# USB2_0.net
KiCad netlist of a schematic drawn in Altium Designer
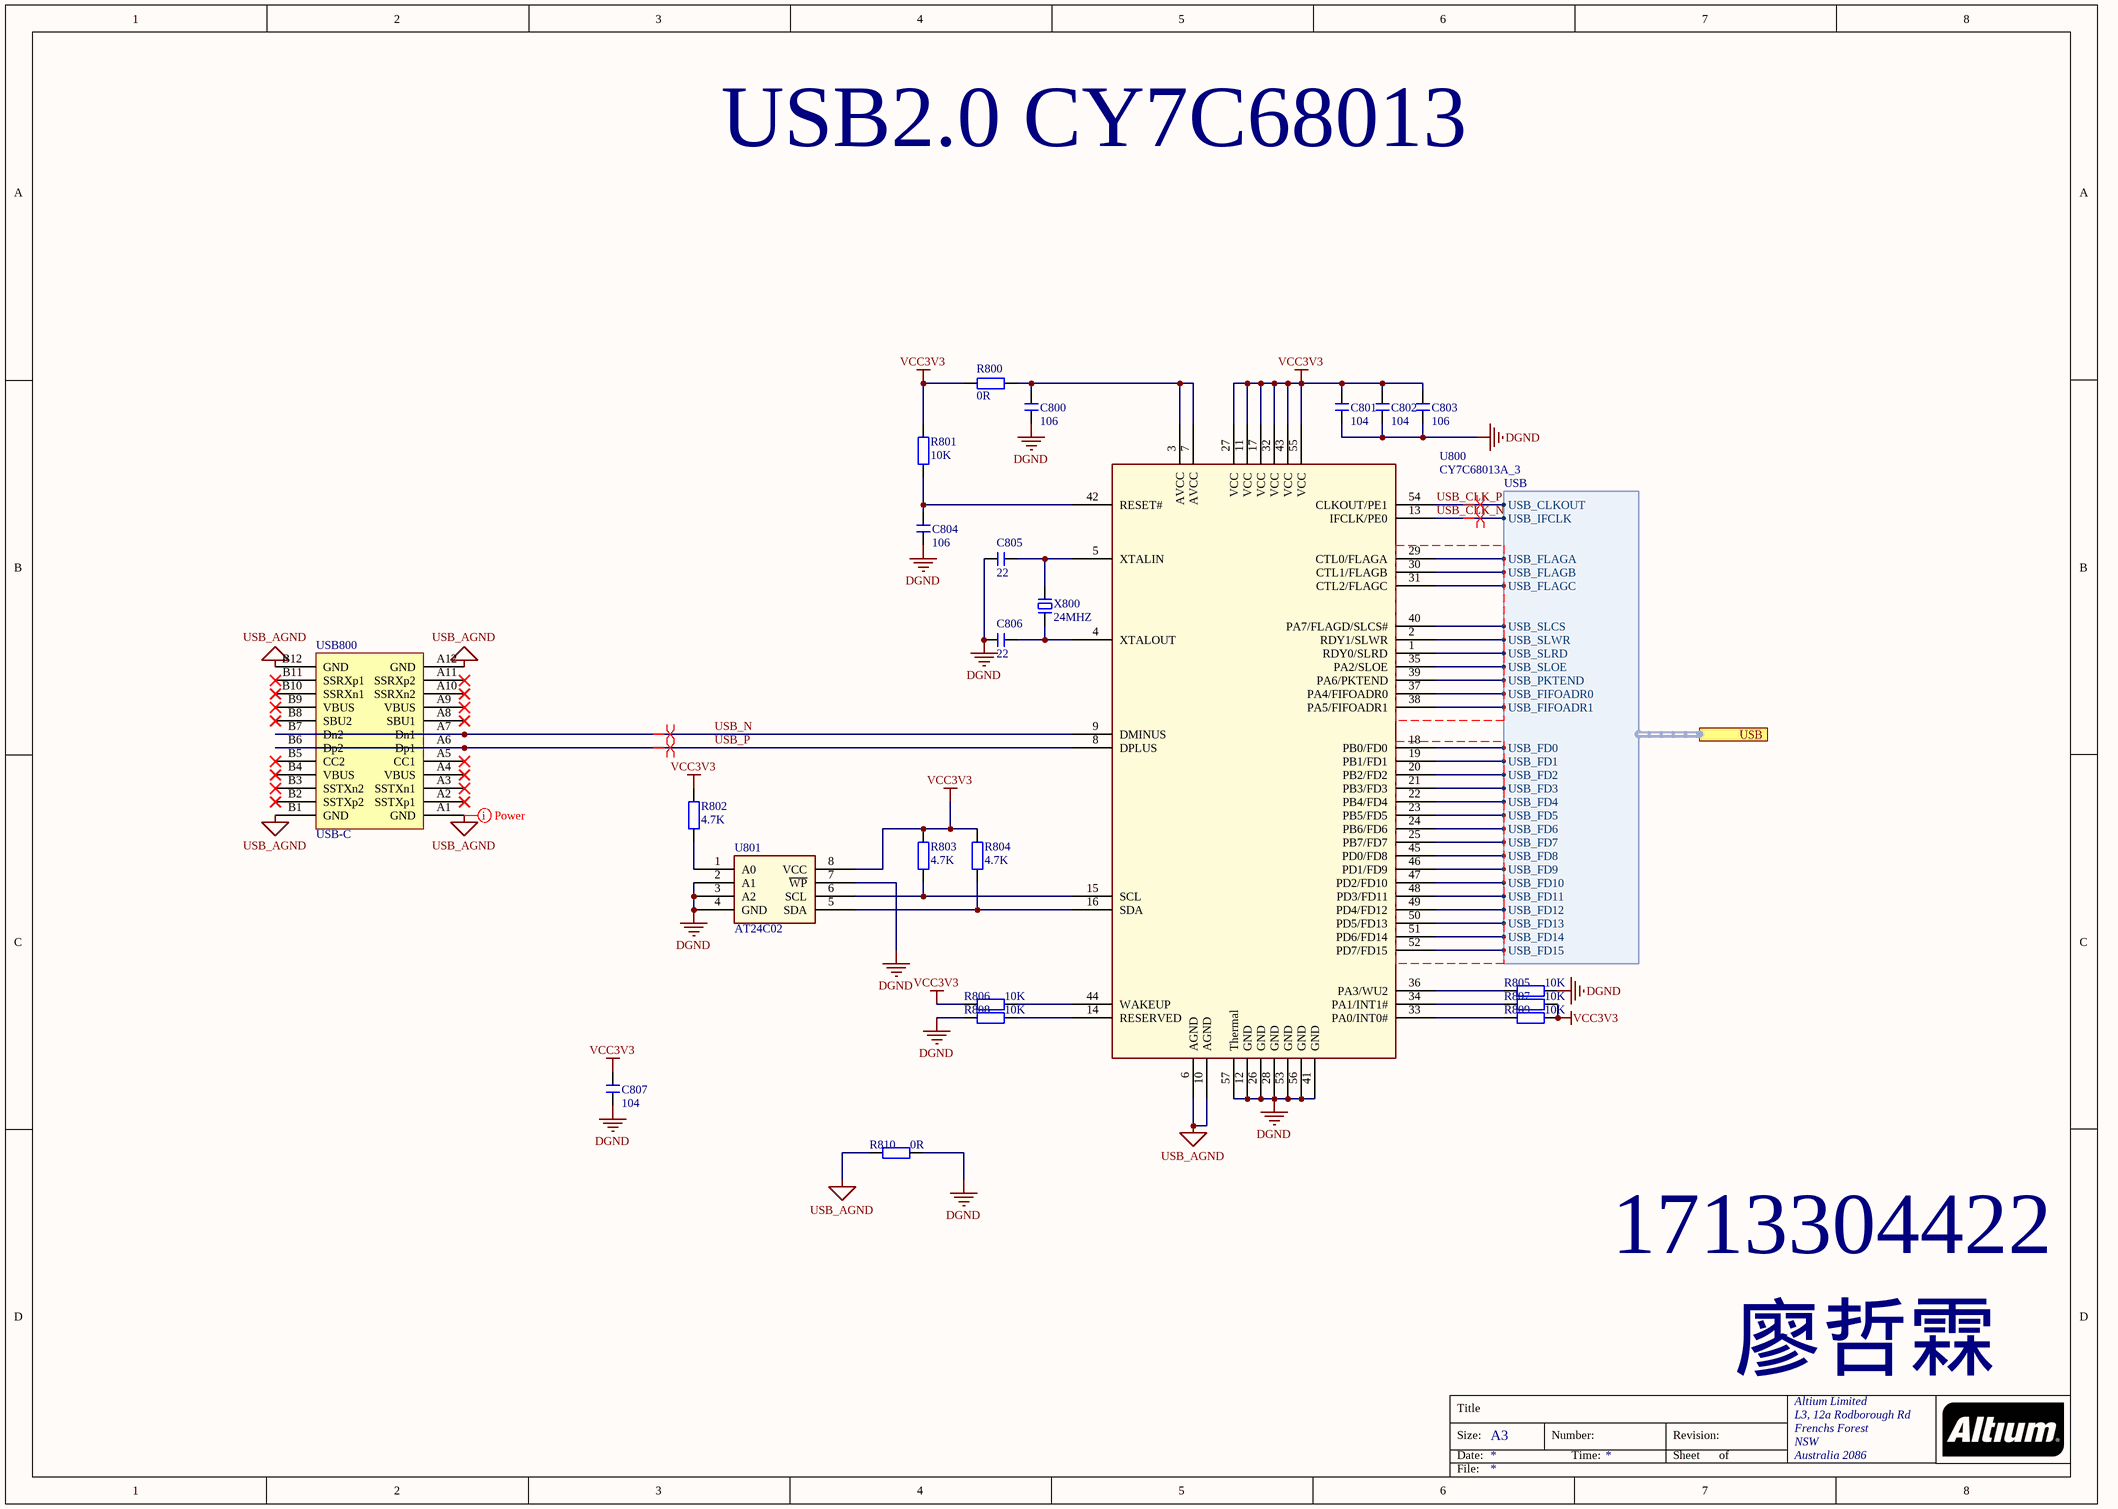
[diagram p0: USB2.0.SchDoc]

(export (version "E")
  (design (tool "Eeschema 10.0.6"))
  (components
    (comp (ref "C800")
      (value "106")
      (footprint "C 0402_M")
      (description "无极性贴片电容")
      (fields (field (name "版权归属") "源创客"))
      (libsource (lib "3.1   - 电阻-电容-电感") (part "C"))
    )
    (comp (ref "C801")
      (value "104")
      (footprint "C 0402_M")
      (description "无极性贴片电容")
      (fields (field (name "版权归属") "源创客"))
      (libsource (lib "3.1   - 电阻-电容-电感") (part "C"))
    )
    (comp (ref "C802")
      (value "104")
      (footprint "C 0402_M")
      (description "无极性贴片电容")
      (fields (field (name "版权归属") "源创客"))
      (libsource (lib "3.1   - 电阻-电容-电感") (part "C"))
    )
    (comp (ref "C803")
      (value "106")
      (footprint "C 0402_M")
      (description "无极性贴片电容")
      (fields (field (name "版权归属") "源创客"))
      (libsource (lib "3.1   - 电阻-电容-电感") (part "C"))
    )
    (comp (ref "C804")
      (value "106")
      (footprint "C 0402_M")
      (description "无极性贴片电容")
      (fields (field (name "版权归属") "源创客"))
      (libsource (lib "3.1   - 电阻-电容-电感") (part "C"))
    )
    (comp (ref "C805")
      (value "22")
      (footprint "C 0402_M")
      (description "无极性贴片电容")
      (fields (field (name "版权归属") "源创客"))
      (libsource (lib "3.1   - 电阻-电容-电感") (part "C"))
    )
    (comp (ref "C806")
      (value "22")
      (footprint "C 0402_M")
      (description "无极性贴片电容")
      (fields (field (name "版权归属") "源创客"))
      (libsource (lib "3.1   - 电阻-电容-电感") (part "C"))
    )
    (comp (ref "C807")
      (value "104")
      (footprint "C 0402_M")
      (description "无极性贴片电容")
      (fields (field (name "版权归属") "源创客"))
      (libsource (lib "3.1   - 电阻-电容-电感") (part "C"))
    )
    (comp (ref "R800")
      (value "0R")
      (footprint "R 0402_M")
      (description "贴片电阻")
      (fields (field (name "版权归属") "源创客"))
      (libsource (lib "3.1   - 电阻-电容-电感") (part "R"))
    )
    (comp (ref "R801")
      (value "10K")
      (footprint "R 0402_M")
      (description "贴片电阻")
      (fields (field (name "版权归属") "源创客"))
      (libsource (lib "3.1   - 电阻-电容-电感") (part "R"))
    )
    (comp (ref "R802")
      (value "4.7K")
      (footprint "R 0402_M")
      (description "贴片电阻")
      (fields (field (name "版权归属") "源创客"))
      (libsource (lib "3.1   - 电阻-电容-电感") (part "R"))
    )
    (comp (ref "R803")
      (value "4.7K")
      (footprint "R 0402_M")
      (description "贴片电阻")
      (fields (field (name "版权归属") "源创客"))
      (libsource (lib "3.1   - 电阻-电容-电感") (part "R"))
    )
    (comp (ref "R804")
      (value "4.7K")
      (footprint "R 0402_M")
      (description "贴片电阻")
      (fields (field (name "版权归属") "源创客"))
      (libsource (lib "3.1   - 电阻-电容-电感") (part "R"))
    )
    (comp (ref "R805")
      (value "10K")
      (footprint "R 0402_M")
      (description "贴片电阻")
      (fields (field (name "版权归属") "源创客"))
      (libsource (lib "3.1   - 电阻-电容-电感") (part "R"))
    )
    (comp (ref "R806")
      (value "10K")
      (footprint "R 0402_M")
      (description "贴片电阻")
      (fields (field (name "版权归属") "源创客"))
      (libsource (lib "3.1   - 电阻-电容-电感") (part "R"))
    )
    (comp (ref "R807")
      (value "10K")
      (footprint "R 0402_M")
      (description "贴片电阻")
      (fields (field (name "版权归属") "源创客"))
      (libsource (lib "3.1   - 电阻-电容-电感") (part "R"))
    )
    (comp (ref "R808")
      (value "10K")
      (footprint "R 0402_M")
      (description "贴片电阻")
      (fields (field (name "版权归属") "源创客"))
      (libsource (lib "3.1   - 电阻-电容-电感") (part "R"))
    )
    (comp (ref "R809")
      (value "10K")
      (footprint "R 0402_M")
      (description "贴片电阻")
      (fields (field (name "版权归属") "源创客"))
      (libsource (lib "3.1   - 电阻-电容-电感") (part "R"))
    )
    (comp (ref "R810")
      (value "0R")
      (footprint "R 0402_M")
      (description "贴片电阻")
      (fields (field (name "版权归属") "源创客"))
      (libsource (lib "3.1   - 电阻-电容-电感") (part "R"))
    )
    (comp (ref "U800")
      (value "CY7C68013A_3")
      (footprint "QFN50P800X800X100-57N")
      (libsource (lib "altium-import") (part "root_0_CY7C68013A_3_"))
    )
    (comp (ref "U801")
      (value "AT24C02")
      (footprint "SOP8_M")
      (libsource (lib "6_Layer_Library") (part "AT24C02"))
    )
    (comp (ref "USB800")
      (value "USB-C")
      (footprint "USB-C/S_A")
      (description "USB-C型母接口")
      (fields (field (name "版权归属") "源创客"))
      (libsource (lib "4.1   - 接口类") (part "USB-C/S"))
    )
    (comp (ref "X800")
      (value "24MHZ")
      (footprint "OSC 5032-2P")
      (description "2脚无源脚晶振")
      (fields (field (name "版权归属") "源创客"))
      (libsource (lib "10.1 - 保险丝-晶振") (part "XTAL-2P"))
    )
  )
  (nets
    (net (code "2") (name "/USB_CLK_N") (class "Default")
      (node (ref "U800") (pin "13") (pinfunction "IFCLK/PE0_13") (pintype "passive"))
    )
    (net (code "3") (name "/USB_CLK_P") (class "Default")
      (node (ref "U800") (pin "54") (pinfunction "CLKOUT/PE1_54") (pintype "passive"))
    )
    (net (code "4") (name "/USB_FD0") (class "Default")
      (node (ref "U800") (pin "18") (pinfunction "PB0/FD0_18") (pintype "passive"))
    )
    (net (code "5") (name "/USB_FD1") (class "Default")
      (node (ref "U800") (pin "19") (pinfunction "PB1/FD1_19") (pintype "passive"))
    )
    (net (code "6") (name "/USB_FD2") (class "Default")
      (node (ref "U800") (pin "20") (pinfunction "PB2/FD2_20") (pintype "passive"))
    )
    (net (code "7") (name "/USB_FD3") (class "Default")
      (node (ref "U800") (pin "21") (pinfunction "PB3/FD3_21") (pintype "passive"))
    )
    (net (code "8") (name "/USB_FD4") (class "Default")
      (node (ref "U800") (pin "22") (pinfunction "PB4/FD4_22") (pintype "passive"))
    )
    (net (code "9") (name "/USB_FD5") (class "Default")
      (node (ref "U800") (pin "23") (pinfunction "PB5/FD5_23") (pintype "passive"))
    )
    (net (code "10") (name "/USB_FD6") (class "Default")
      (node (ref "U800") (pin "24") (pinfunction "PB6/FD6_24") (pintype "passive"))
    )
    (net (code "11") (name "/USB_FD7") (class "Default")
      (node (ref "U800") (pin "25") (pinfunction "PB7/FD7_25") (pintype "passive"))
    )
    (net (code "12") (name "/USB_FD8") (class "Default")
      (node (ref "U800") (pin "45") (pinfunction "PD0/FD8_45") (pintype "passive"))
    )
    (net (code "13") (name "/USB_FD9") (class "Default")
      (node (ref "U800") (pin "46") (pinfunction "PD1/FD9_46") (pintype "passive"))
    )
    (net (code "14") (name "/USB_FD10") (class "Default")
      (node (ref "U800") (pin "47") (pinfunction "PD2/FD10_47") (pintype "passive"))
    )
    (net (code "15") (name "/USB_FD11") (class "Default")
      (node (ref "U800") (pin "48") (pinfunction "PD3/FD11_48") (pintype "passive"))
    )
    (net (code "16") (name "/USB_FD12") (class "Default")
      (node (ref "U800") (pin "49") (pinfunction "PD4/FD12_49") (pintype "passive"))
    )
    (net (code "17") (name "/USB_FD13") (class "Default")
      (node (ref "U800") (pin "50") (pinfunction "PD5/FD13_50") (pintype "passive"))
    )
    (net (code "18") (name "/USB_FD14") (class "Default")
      (node (ref "U800") (pin "51") (pinfunction "PD6/FD14_51") (pintype "passive"))
    )
    (net (code "19") (name "/USB_FD15") (class "Default")
      (node (ref "U800") (pin "52") (pinfunction "PD7/FD15_52") (pintype "passive"))
    )
    (net (code "20") (name "/USB_FIFOADR0") (class "Default")
      (node (ref "U800") (pin "37") (pinfunction "PA4/FIFOADR0_37") (pintype "passive"))
    )
    (net (code "21") (name "/USB_FIFOADR1") (class "Default")
      (node (ref "U800") (pin "38") (pinfunction "PA5/FIFOADR1_38") (pintype "passive"))
    )
    (net (code "22") (name "/USB_FLAGA") (class "Default")
      (node (ref "U800") (pin "29") (pinfunction "CTL0/FLAGA_29") (pintype "passive"))
    )
    (net (code "23") (name "/USB_FLAGB") (class "Default")
      (node (ref "U800") (pin "30") (pinfunction "CTL1/FLAGB_30") (pintype "passive"))
    )
    (net (code "24") (name "/USB_FLAGC") (class "Default")
      (node (ref "U800") (pin "31") (pinfunction "CTL2/FLAGC_31") (pintype "passive"))
    )
    (net (code "25") (name "/USB_N") (class "Default")
      (node (ref "U800") (pin "9") (pinfunction "DMINUS_9") (pintype "passive"))
      (node (ref "USB800") (pin "A7") (pinfunction "Dn1_A7") (pintype "passive"))
      (node (ref "USB800") (pin "B7") (pinfunction "Dn2_B7") (pintype "passive"))
    )
    (net (code "26") (name "/USB_P") (class "Default")
      (node (ref "U800") (pin "8") (pinfunction "DPLUS_8") (pintype "passive"))
      (node (ref "USB800") (pin "A6") (pinfunction "Dp1_A6") (pintype "passive"))
      (node (ref "USB800") (pin "B6") (pinfunction "Dp2_B6") (pintype "passive"))
    )
    (net (code "27") (name "/USB_PKTEND") (class "Default")
      (node (ref "U800") (pin "39") (pinfunction "PA6/PKTEND_39") (pintype "passive"))
    )
    (net (code "28") (name "/USB_SLCS") (class "Default")
      (node (ref "U800") (pin "40") (pinfunction "PA7/FLAGD/SLCS#_40") (pintype "passive"))
    )
    (net (code "29") (name "/USB_SLOE") (class "Default")
      (node (ref "U800") (pin "35") (pinfunction "PA2/SLOE_35") (pintype "passive"))
    )
    (net (code "30") (name "/USB_SLRD") (class "Default")
      (node (ref "U800") (pin "1") (pinfunction "RDY0/SLRD_1") (pintype "passive"))
    )
    (net (code "31") (name "/USB_SLWR") (class "Default")
      (node (ref "U800") (pin "2") (pinfunction "RDY1/SLWR_2") (pintype "passive"))
    )
    (net (code "33") (name "DGND") (class "Default")
      (node (ref "C800") (pin "1") (pinfunction "1_1") (pintype "passive"))
      (node (ref "C801") (pin "1") (pinfunction "1_1") (pintype "passive"))
      (node (ref "C802") (pin "1") (pinfunction "1_1") (pintype "passive"))
      (node (ref "C803") (pin "1") (pinfunction "1_1") (pintype "passive"))
      (node (ref "C804") (pin "1") (pinfunction "1_1") (pintype "passive"))
      (node (ref "C805") (pin "2") (pinfunction "2_2") (pintype "passive"))
      (node (ref "C806") (pin "2") (pinfunction "2_2") (pintype "passive"))
      (node (ref "C807") (pin "2") (pinfunction "2_2") (pintype "passive"))
      (node (ref "R805") (pin "2") (pinfunction "2_2") (pintype "passive"))
      (node (ref "R808") (pin "1") (pinfunction "1_1") (pintype "passive"))
      (node (ref "R810") (pin "2") (pinfunction "2_2") (pintype "passive"))
      (node (ref "U800") (pin "12") (pinfunction "GND_12") (pintype "power_in"))
      (node (ref "U800") (pin "26") (pinfunction "GND_26") (pintype "power_in"))
      (node (ref "U800") (pin "28") (pinfunction "GND_28") (pintype "power_in"))
      (node (ref "U800") (pin "41") (pinfunction "GND_41") (pintype "power_in"))
      (node (ref "U800") (pin "53") (pinfunction "GND_53") (pintype "power_in"))
      (node (ref "U800") (pin "56") (pinfunction "GND_56") (pintype "power_in"))
      (node (ref "U800") (pin "57") (pinfunction "Thermal_57") (pintype "power_in"))
      (node (ref "U801") (pin "2") (pinfunction "A1_2") (pintype "power_in"))
      (node (ref "U801") (pin "3") (pinfunction "A2_3") (pintype "power_in"))
      (node (ref "U801") (pin "4") (pinfunction "GND_4") (pintype "passive"))
      (node (ref "U801") (pin "7") (pinfunction "~{WP}_7") (pintype "passive"))
    )
    (net (code "34") (name "Net-(C800-Pad2)") (class "Default")
      (node (ref "C800") (pin "2") (pinfunction "2_2") (pintype "passive"))
      (node (ref "R800") (pin "1") (pinfunction "1_1") (pintype "passive"))
      (node (ref "U800") (pin "3") (pinfunction "AVCC_3") (pintype "power_in"))
      (node (ref "U800") (pin "7") (pinfunction "AVCC_7") (pintype "power_in"))
    )
    (net (code "35") (name "Net-(U800-PA0{slash}INT0#)") (class "Default")
      (node (ref "R809") (pin "1") (pinfunction "1_1") (pintype "passive"))
      (node (ref "U800") (pin "33") (pinfunction "PA0/INT0#_33") (pintype "passive"))
    )
    (net (code "36") (name "Net-(U800-PA1{slash}INT1#)") (class "Default")
      (node (ref "R807") (pin "1") (pinfunction "1_1") (pintype "passive"))
      (node (ref "U800") (pin "34") (pinfunction "PA1/INT1#_34") (pintype "passive"))
    )
    (net (code "37") (name "Net-(U800-PA3{slash}WU2)") (class "Default")
      (node (ref "R805") (pin "1") (pinfunction "1_1") (pintype "passive"))
      (node (ref "U800") (pin "36") (pinfunction "PA3/WU2_36") (pintype "passive"))
    )
    (net (code "38") (name "Net-(U800-RESERVED)") (class "Default")
      (node (ref "R808") (pin "2") (pinfunction "2_2") (pintype "passive"))
      (node (ref "U800") (pin "14") (pinfunction "RESERVED_14") (pintype "passive"))
    )
    (net (code "39") (name "Net-(U800-RESET#)") (class "Default")
      (node (ref "C804") (pin "2") (pinfunction "2_2") (pintype "passive"))
      (node (ref "R801") (pin "2") (pinfunction "2_2") (pintype "passive"))
      (node (ref "U800") (pin "42") (pinfunction "RESET#_42") (pintype "power_in"))
    )
    (net (code "40") (name "Net-(U800-SCL)") (class "Default")
      (node (ref "R803") (pin "2") (pinfunction "2_2") (pintype "passive"))
      (node (ref "U800") (pin "15") (pinfunction "SCL_15") (pintype "passive"))
      (node (ref "U801") (pin "6") (pinfunction "SCL_6") (pintype "passive"))
    )
    (net (code "41") (name "Net-(U800-SDA)") (class "Default")
      (node (ref "R804") (pin "2") (pinfunction "2_2") (pintype "passive"))
      (node (ref "U800") (pin "16") (pinfunction "SDA_16") (pintype "passive"))
      (node (ref "U801") (pin "5") (pinfunction "SDA_5") (pintype "passive"))
    )
    (net (code "42") (name "Net-(U800-WAKEUP)") (class "Default")
      (node (ref "R806") (pin "2") (pinfunction "2_2") (pintype "passive"))
      (node (ref "U800") (pin "44") (pinfunction "WAKEUP_44") (pintype "passive"))
    )
    (net (code "43") (name "Net-(U800-XTALIN)") (class "Default")
      (node (ref "C805") (pin "1") (pinfunction "1_1") (pintype "passive"))
      (node (ref "U800") (pin "5") (pinfunction "XTALIN_5") (pintype "passive"))
      (node (ref "X800") (pin "2") (pinfunction "2_2") (pintype "passive"))
    )
    (net (code "44") (name "Net-(U800-XTALOUT)") (class "Default")
      (node (ref "C806") (pin "1") (pinfunction "1_1") (pintype "passive"))
      (node (ref "U800") (pin "4") (pinfunction "XTALOUT_4") (pintype "passive"))
      (node (ref "X800") (pin "1") (pinfunction "1_1") (pintype "passive"))
    )
    (net (code "45") (name "Net-(U801-A0)") (class "Default")
      (node (ref "R802") (pin "2") (pinfunction "2_2") (pintype "passive"))
      (node (ref "U801") (pin "1") (pinfunction "A0_1") (pintype "power_in"))
    )
    (net (code "46") (name "USB_AGND") (class "Default")
      (node (ref "R810") (pin "1") (pinfunction "1_1") (pintype "passive"))
      (node (ref "U800") (pin "10") (pinfunction "AGND_10") (pintype "power_in"))
      (node (ref "U800") (pin "6") (pinfunction "AGND_6") (pintype "power_in"))
      (node (ref "USB800") (pin "A1") (pinfunction "GND_A1") (pintype "passive"))
      (node (ref "USB800") (pin "A12") (pinfunction "GND_A12") (pintype "passive"))
      (node (ref "USB800") (pin "B1") (pinfunction "GND_B1") (pintype "passive"))
      (node (ref "USB800") (pin "B12") (pinfunction "GND_B12") (pintype "passive"))
    )
    (net (code "47") (name "VCC3V3") (class "Default")
      (node (ref "C801") (pin "2") (pinfunction "2_2") (pintype "passive"))
      (node (ref "C802") (pin "2") (pinfunction "2_2") (pintype "passive"))
      (node (ref "C803") (pin "2") (pinfunction "2_2") (pintype "passive"))
      (node (ref "C807") (pin "1") (pinfunction "1_1") (pintype "passive"))
      (node (ref "R800") (pin "2") (pinfunction "2_2") (pintype "passive"))
      (node (ref "R801") (pin "1") (pinfunction "1_1") (pintype "passive"))
      (node (ref "R802") (pin "1") (pinfunction "1_1") (pintype "passive"))
      (node (ref "R803") (pin "1") (pinfunction "1_1") (pintype "passive"))
      (node (ref "R804") (pin "1") (pinfunction "1_1") (pintype "passive"))
      (node (ref "R806") (pin "1") (pinfunction "1_1") (pintype "passive"))
      (node (ref "R807") (pin "2") (pinfunction "2_2") (pintype "passive"))
      (node (ref "R809") (pin "2") (pinfunction "2_2") (pintype "passive"))
      (node (ref "U800") (pin "11") (pinfunction "VCC_11") (pintype "power_in"))
      (node (ref "U800") (pin "17") (pinfunction "VCC_17") (pintype "power_in"))
      (node (ref "U800") (pin "27") (pinfunction "VCC_27") (pintype "power_in"))
      (node (ref "U800") (pin "32") (pinfunction "VCC_32") (pintype "power_in"))
      (node (ref "U800") (pin "43") (pinfunction "VCC_43") (pintype "power_in"))
      (node (ref "U800") (pin "55") (pinfunction "VCC_55") (pintype "power_in"))
      (node (ref "U801") (pin "8") (pinfunction "VCC_8") (pintype "passive"))
    )
    (net (code "48") (name "unconnected-(USB800-CC1-PadA5)") (class "Default")
      (node (ref "USB800") (pin "A5") (pinfunction "CC1_A5") (pintype "passive+no_connect"))
    )
    (net (code "49") (name "unconnected-(USB800-CC2-PadB5)") (class "Default")
      (node (ref "USB800") (pin "B5") (pinfunction "CC2_B5") (pintype "passive+no_connect"))
    )
    (net (code "50") (name "unconnected-(USB800-SBU1-PadA8)") (class "Default")
      (node (ref "USB800") (pin "A8") (pinfunction "SBU1_A8") (pintype "passive+no_connect"))
    )
    (net (code "51") (name "unconnected-(USB800-SBU2-PadB8)") (class "Default")
      (node (ref "USB800") (pin "B8") (pinfunction "SBU2_B8") (pintype "passive+no_connect"))
    )
    (net (code "52") (name "unconnected-(USB800-SSRXn1-PadB10)") (class "Default")
      (node (ref "USB800") (pin "B10") (pinfunction "SSRXn1_B10") (pintype "passive+no_connect"))
    )
    (net (code "53") (name "unconnected-(USB800-SSRXn2-PadA10)") (class "Default")
      (node (ref "USB800") (pin "A10") (pinfunction "SSRXn2_A10") (pintype "passive+no_connect"))
    )
    (net (code "54") (name "unconnected-(USB800-SSRXp1-PadB11)") (class "Default")
      (node (ref "USB800") (pin "B11") (pinfunction "SSRXp1_B11") (pintype "passive+no_connect"))
    )
    (net (code "55") (name "unconnected-(USB800-SSRXp2-PadA11)") (class "Default")
      (node (ref "USB800") (pin "A11") (pinfunction "SSRXp2_A11") (pintype "passive+no_connect"))
    )
    (net (code "56") (name "unconnected-(USB800-SSTXn1-PadA3)") (class "Default")
      (node (ref "USB800") (pin "A3") (pinfunction "SSTXn1_A3") (pintype "passive+no_connect"))
    )
    (net (code "57") (name "unconnected-(USB800-SSTXn2-PadB3)") (class "Default")
      (node (ref "USB800") (pin "B3") (pinfunction "SSTXn2_B3") (pintype "passive+no_connect"))
    )
    (net (code "58") (name "unconnected-(USB800-SSTXp1-PadA2)") (class "Default")
      (node (ref "USB800") (pin "A2") (pinfunction "SSTXp1_A2") (pintype "passive+no_connect"))
    )
    (net (code "59") (name "unconnected-(USB800-SSTXp2-PadB2)") (class "Default")
      (node (ref "USB800") (pin "B2") (pinfunction "SSTXp2_B2") (pintype "passive+no_connect"))
    )
    (net (code "60") (name "unconnected-(USB800-VBUS-PadA4)") (class "Default")
      (node (ref "USB800") (pin "A4") (pinfunction "VBUS_A4") (pintype "passive+no_connect"))
    )
    (net (code "61") (name "unconnected-(USB800-VBUS-PadA9)") (class "Default")
      (node (ref "USB800") (pin "A9") (pinfunction "VBUS_A9") (pintype "passive+no_connect"))
    )
    (net (code "62") (name "unconnected-(USB800-VBUS-PadB4)") (class "Default")
      (node (ref "USB800") (pin "B4") (pinfunction "VBUS_B4") (pintype "passive+no_connect"))
    )
    (net (code "63") (name "unconnected-(USB800-VBUS-PadB9)") (class "Default")
      (node (ref "USB800") (pin "B9") (pinfunction "VBUS_B9") (pintype "passive+no_connect"))
    )
  )
)
